# Domino_Dual_Ethernet.net
KiCad netlist of a schematic drawn in EAGLE
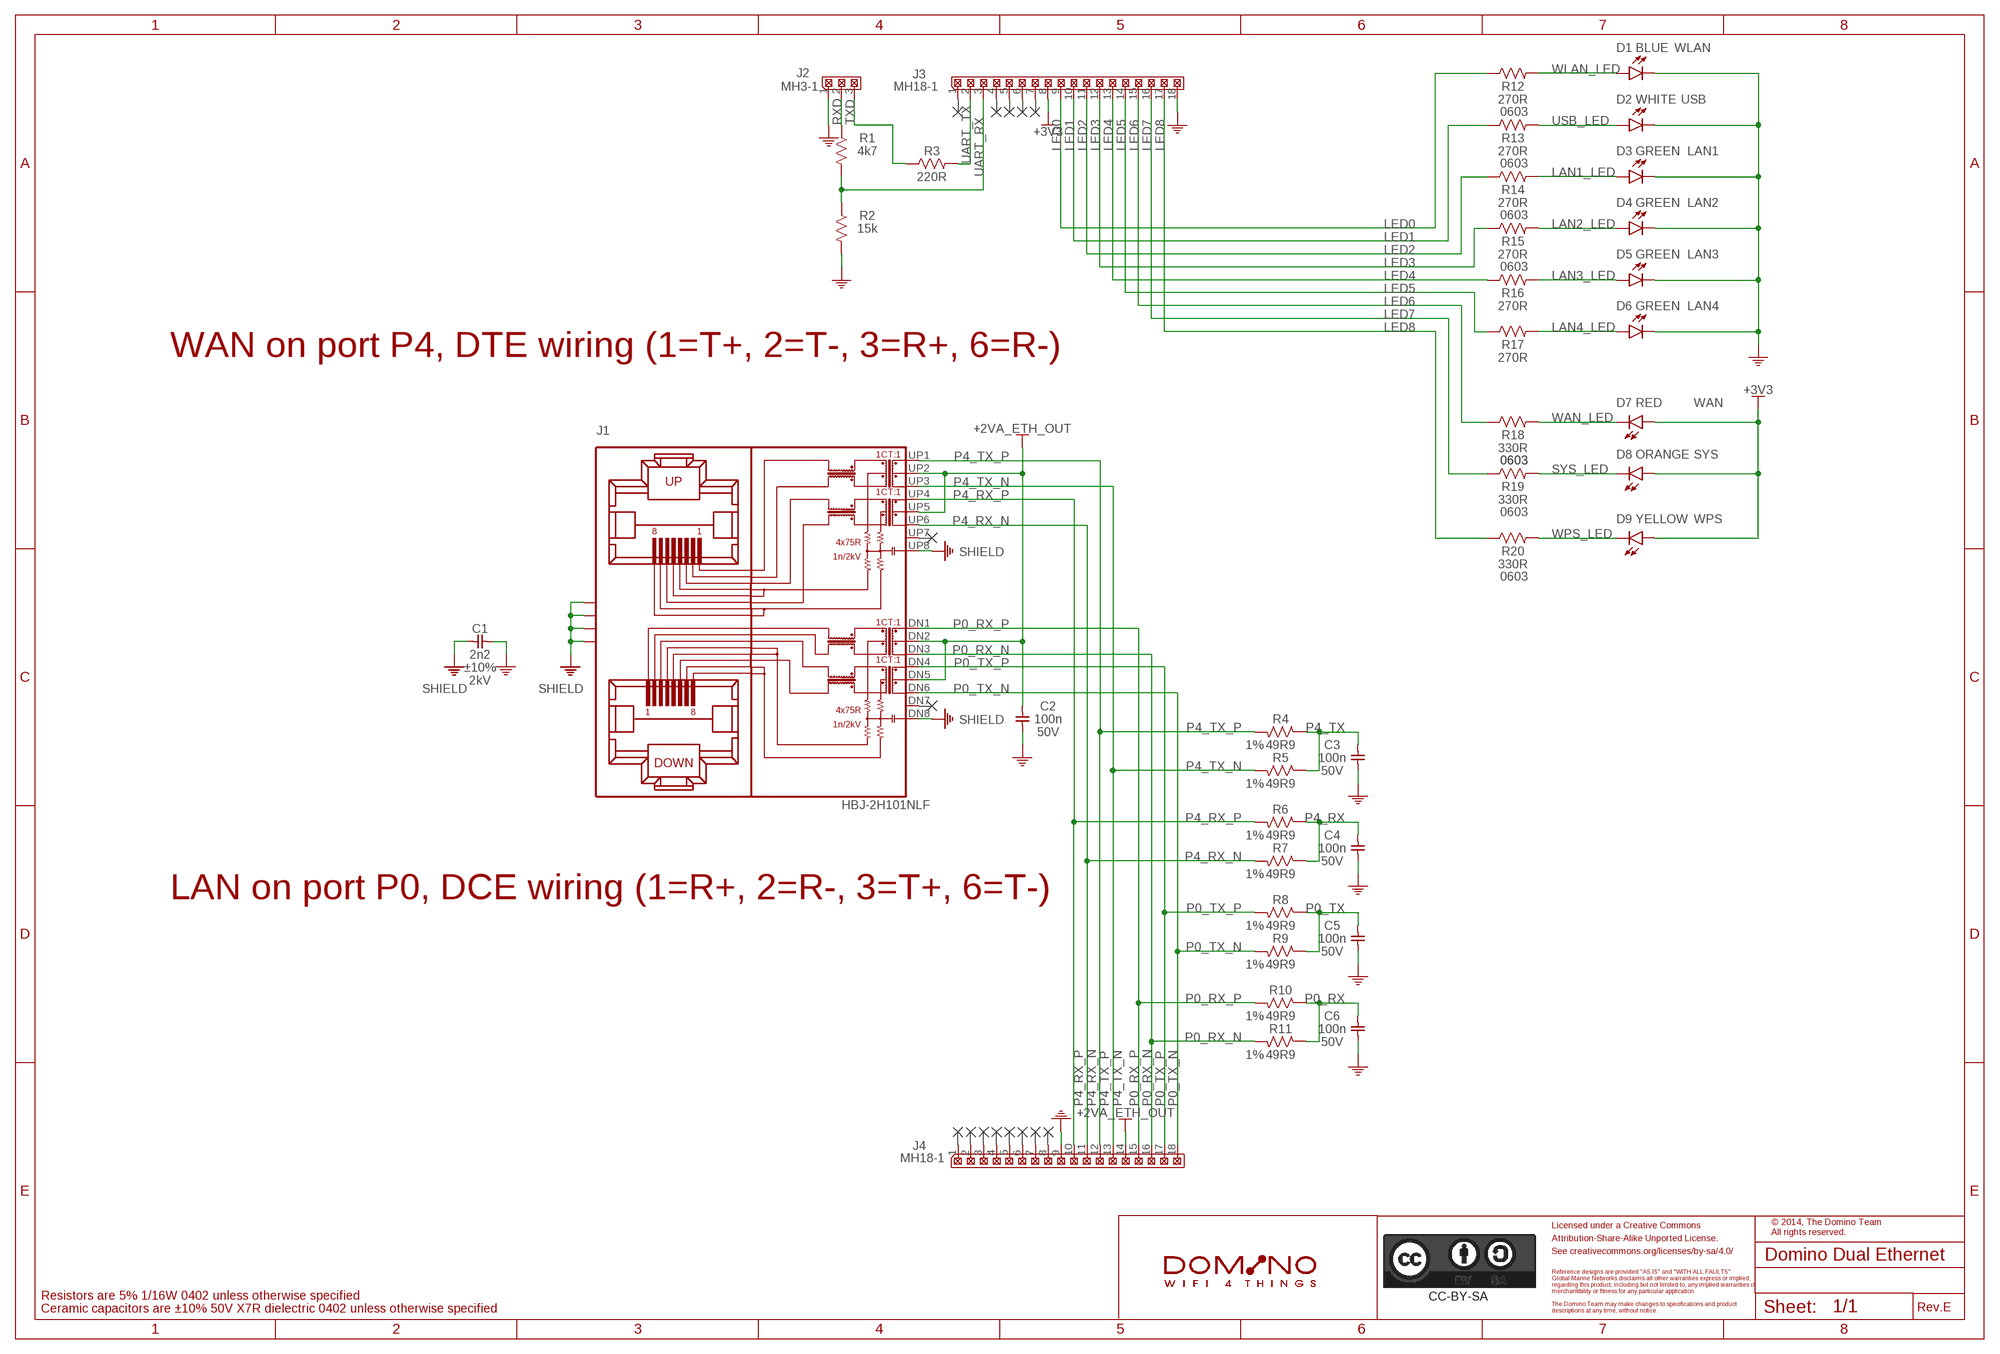
[diagram p0: schematic, sheet 1]

(export (version "E")
  (design (tool "Eeschema 10.0.6"))
  (components
    (comp (ref "C1")
      (value "2n2")
      (footprint "eagle-import:C1206")
      (fields
        (field (name "PARTNO") "C1210_2n2_X7R_10%_CER_2kV")
        (field (name "TOL") "±10%")
        (field (name "VOLT") "2kV")
      )
      (libsource (lib "eagle-import") (part "CAP_1206"))
    )
    (comp (ref "C2")
      (value "100n")
      (footprint "eagle-import:C0402")
      (fields (field (name "PARTNO") "C0402_100n_X7R_10%_CER_50V") (field (name "VOLT") "50V"))
      (libsource (lib "eagle-import") (part "CAP_0402"))
    )
    (comp (ref "C3")
      (value "100n")
      (footprint "eagle-import:C0402")
      (fields (field (name "PARTNO") "C0402_100n_X7R_10%_CER_50V") (field (name "VOLT") "50V"))
      (libsource (lib "eagle-import") (part "CAP_0402"))
    )
    (comp (ref "C4")
      (value "100n")
      (footprint "eagle-import:C0402")
      (fields (field (name "PARTNO") "C0402_100n_X7R_10%_CER_50V") (field (name "VOLT") "50V"))
      (libsource (lib "eagle-import") (part "CAP_0402"))
    )
    (comp (ref "C5")
      (value "100n")
      (footprint "eagle-import:C0402")
      (fields (field (name "PARTNO") "C0402_100n_X7R_10%_CER_50V") (field (name "VOLT") "50V"))
      (libsource (lib "eagle-import") (part "CAP_0402"))
    )
    (comp (ref "C6")
      (value "100n")
      (footprint "eagle-import:C0402")
      (fields (field (name "PARTNO") "C0402_100n_X7R_10%_CER_50V") (field (name "VOLT") "50V"))
      (libsource (lib "eagle-import") (part "CAP_0402"))
    )
    (comp (ref "CC-BY-SA1")
      (value "CC-BY-SA_LOGO")
      (footprint "eagle-import:CC-BY-SA_LOGO")
      (libsource (lib "eagle-import") (part "CC-BY-SA_LOGO"))
    )
    (comp (ref "D1")
      (value "BLUE")
      (footprint "eagle-import:LED0603")
      (fields (field (name "PARTNO") "LED0603-BLUE"))
      (libsource (lib "eagle-import") (part "LED_0603"))
    )
    (comp (ref "D2")
      (value "WHITE")
      (footprint "eagle-import:LED0603")
      (fields (field (name "PARTNO") "LED0603-WHITE"))
      (libsource (lib "eagle-import") (part "LED_0603"))
    )
    (comp (ref "D3")
      (value "GREEN")
      (footprint "eagle-import:LED0603")
      (fields (field (name "PARTNO") "LED0603-GREEN"))
      (libsource (lib "eagle-import") (part "LED_0603"))
    )
    (comp (ref "D4")
      (value "GREEN")
      (footprint "eagle-import:LED0603")
      (fields (field (name "PARTNO") "LED0603-GREEN"))
      (libsource (lib "eagle-import") (part "LED_0603"))
    )
    (comp (ref "D5")
      (value "GREEN")
      (footprint "eagle-import:LED0603")
      (fields (field (name "PARTNO") "LED0603-GREEN"))
      (libsource (lib "eagle-import") (part "LED_0603"))
    )
    (comp (ref "D6")
      (value "GREEN")
      (footprint "eagle-import:LED0603")
      (fields (field (name "PARTNO") "LED0603-GREEN"))
      (libsource (lib "eagle-import") (part "LED_0603"))
    )
    (comp (ref "D7")
      (value "RED")
      (footprint "eagle-import:LED0603")
      (fields (field (name "PARTNO") "LED0603-ORANGE"))
      (libsource (lib "eagle-import") (part "LED_0603"))
    )
    (comp (ref "D8")
      (value "ORANGE")
      (footprint "eagle-import:LED0603")
      (fields (field (name "PARTNO") "LED0603-ORANGE"))
      (libsource (lib "eagle-import") (part "LED_0603"))
    )
    (comp (ref "D9")
      (value "YELLOW")
      (footprint "eagle-import:LED0603")
      (fields (field (name "PARTNO") "LED0603-YELLOW"))
      (libsource (lib "eagle-import") (part "LED_0603"))
    )
    (comp (ref "J1")
      (value "HBJ-2H101NLF")
      (footprint "eagle-import:HBJ-2H101NLF")
      (libsource (lib "eagle-import") (part "HBJ-2H101NLF"))
    )
    (comp (ref "J2")
      (value "MH3-1")
      (footprint "eagle-import:MH3-1-0.1")
      (fields (field (name "PARTNO") "MH3-1-0.1"))
      (libsource (lib "eagle-import") (part "MH3-1"))
    )
    (comp (ref "J3")
      (value "MH18-1")
      (footprint "eagle-import:MH18-1-0.1")
      (fields (field (name "PARTNO") "MH18-1-0.1"))
      (libsource (lib "eagle-import") (part "MH18-1"))
    )
    (comp (ref "J4")
      (value "MH18-1")
      (footprint "eagle-import:MH18-1-0.1")
      (fields (field (name "PARTNO") "MH18-1-0.1"))
      (libsource (lib "eagle-import") (part "MH18-1"))
    )
    (comp (ref "L1")
      (value "DOMINO_LOGO")
      (footprint "eagle-import:DOMINO_LOGO")
      (libsource (lib "eagle-import") (part "DOMINO_LOGO"))
    )
    (comp (ref "R1")
      (value "4k7")
      (footprint "eagle-import:R0402")
      (fields (field (name "PARTNO") "R0402_4k7_5%_62.5mW"))
      (libsource (lib "eagle-import") (part "RES_0402"))
    )
    (comp (ref "R2")
      (value "15k")
      (footprint "eagle-import:R0402")
      (fields (field (name "PARTNO") "R0402_15k_5%_62.5mW"))
      (libsource (lib "eagle-import") (part "RES_0402"))
    )
    (comp (ref "R3")
      (value "220R")
      (footprint "eagle-import:R0402")
      (fields (field (name "PARTNO") "R0402_220R_5%_62.5mW"))
      (libsource (lib "eagle-import") (part "RES_0402"))
    )
    (comp (ref "R4")
      (value "49R9")
      (footprint "eagle-import:R0402")
      (fields (field (name "PARTNO") "R0402_49R9_1%_62.5mW") (field (name "TOL") "1%"))
      (libsource (lib "eagle-import") (part "RES_0402"))
    )
    (comp (ref "R5")
      (value "49R9")
      (footprint "eagle-import:R0402")
      (fields (field (name "PARTNO") "R0402_49R9_1%_62.5mW") (field (name "TOL") "1%"))
      (libsource (lib "eagle-import") (part "RES_0402"))
    )
    (comp (ref "R6")
      (value "49R9")
      (footprint "eagle-import:R0402")
      (fields (field (name "PARTNO") "R0402_49R9_1%_62.5mW") (field (name "TOL") "1%"))
      (libsource (lib "eagle-import") (part "RES_0402"))
    )
    (comp (ref "R7")
      (value "49R9")
      (footprint "eagle-import:R0402")
      (fields (field (name "PARTNO") "R0402_49R9_1%_62.5mW") (field (name "TOL") "1%"))
      (libsource (lib "eagle-import") (part "RES_0402"))
    )
    (comp (ref "R8")
      (value "49R9")
      (footprint "eagle-import:R0402")
      (fields (field (name "PARTNO") "R0402_49R9_1%_62.5mW") (field (name "TOL") "1%"))
      (libsource (lib "eagle-import") (part "RES_0402"))
    )
    (comp (ref "R9")
      (value "49R9")
      (footprint "eagle-import:R0402")
      (fields (field (name "PARTNO") "R0402_49R9_1%_62.5mW") (field (name "TOL") "1%"))
      (libsource (lib "eagle-import") (part "RES_0402"))
    )
    (comp (ref "R10")
      (value "49R9")
      (footprint "eagle-import:R0402")
      (fields (field (name "PARTNO") "R0402_49R9_1%_62.5mW") (field (name "TOL") "1%"))
      (libsource (lib "eagle-import") (part "RES_0402"))
    )
    (comp (ref "R11")
      (value "49R9")
      (footprint "eagle-import:R0402")
      (fields (field (name "PARTNO") "R0402_49R9_1%_62.5mW") (field (name "TOL") "1%"))
      (libsource (lib "eagle-import") (part "RES_0402"))
    )
    (comp (ref "R12")
      (value "270R")
      (footprint "eagle-import:R0603")
      (fields (field (name "SIZE") "0603") (field (name "PARTNO") "R0603_270R_5%_125mW"))
      (libsource (lib "eagle-import") (part "RES_0603"))
    )
    (comp (ref "R13")
      (value "270R")
      (footprint "eagle-import:R0603")
      (fields (field (name "SIZE") "0603") (field (name "PARTNO") "R0603_270R_5%_125mW"))
      (libsource (lib "eagle-import") (part "RES_0603"))
    )
    (comp (ref "R14")
      (value "270R")
      (footprint "eagle-import:R0603")
      (fields (field (name "SIZE") "0603") (field (name "PARTNO") "R0603_270R_5%_125mW"))
      (libsource (lib "eagle-import") (part "RES_0603"))
    )
    (comp (ref "R15")
      (value "270R")
      (footprint "eagle-import:R0603")
      (fields (field (name "SIZE") "0603") (field (name "PARTNO") "R0603_270R_5%_125mW"))
      (libsource (lib "eagle-import") (part "RES_0603"))
    )
    (comp (ref "R16")
      (value "270R")
      (footprint "eagle-import:R0603")
      (fields (field (name "PARTNO") "R0603_270R_5%_125mW"))
      (libsource (lib "eagle-import") (part "RES_0603"))
    )
    (comp (ref "R17")
      (value "270R")
      (footprint "eagle-import:R0603")
      (fields (field (name "SIZE") "0603") (field (name "PARTNO") "R0603_270R_5%_125mW"))
      (libsource (lib "eagle-import") (part "RES_0603"))
    )
    (comp (ref "R18")
      (value "330R")
      (footprint "eagle-import:R0603")
      (fields (field (name "SIZE") "0603") (field (name "PARTNO") "R0603_330R_5%_125mW"))
      (libsource (lib "eagle-import") (part "RES_0603"))
    )
    (comp (ref "R19")
      (value "330R")
      (footprint "eagle-import:R0603")
      (fields (field (name "SIZE") "0603") (field (name "PARTNO") "R0603_330R_5%_125mW"))
      (libsource (lib "eagle-import") (part "RES_0603"))
    )
    (comp (ref "R20")
      (value "330R")
      (footprint "eagle-import:R0603")
      (fields (field (name "SIZE") "0603") (field (name "PARTNO") "R0603_330R_5%_125mW"))
      (libsource (lib "eagle-import") (part "RES_0603"))
    )
  )
  (nets
    (net (code "1") (name "+2VA_ETH_OUT") (class "Default")
      (node (ref "C2") (pin "2") (pinfunction "2_2") (pintype "passive"))
      (node (ref "J1") (pin "DN2") (pinfunction "DR2_DN2") (pintype "passive"))
      (node (ref "J1") (pin "DN5") (pinfunction "DR5_DN5") (pintype "passive"))
      (node (ref "J1") (pin "UP2") (pinfunction "UR2_UP2") (pintype "passive"))
      (node (ref "J1") (pin "UP5") (pinfunction "UR5_UP5") (pintype "passive"))
      (node (ref "J4") (pin "14") (pinfunction "14_14") (pintype "passive"))
    )
    (net (code "2") (name "+3V3") (class "Default")
      (node (ref "D7") (pin "2") (pinfunction "A_2") (pintype "passive"))
      (node (ref "D8") (pin "2") (pinfunction "A_2") (pintype "passive"))
      (node (ref "D9") (pin "2") (pinfunction "A_2") (pintype "passive"))
      (node (ref "J3") (pin "8") (pinfunction "8_8") (pintype "passive"))
    )
    (net (code "3") (name "/LAN1_LED") (class "Default")
      (node (ref "D3") (pin "2") (pinfunction "A_2") (pintype "passive"))
      (node (ref "R14") (pin "2") (pinfunction "2_2") (pintype "passive"))
    )
    (net (code "4") (name "/LAN2_LED") (class "Default")
      (node (ref "D4") (pin "2") (pinfunction "A_2") (pintype "passive"))
      (node (ref "R15") (pin "2") (pinfunction "2_2") (pintype "passive"))
    )
    (net (code "5") (name "/LAN3_LED") (class "Default")
      (node (ref "D5") (pin "2") (pinfunction "A_2") (pintype "passive"))
      (node (ref "R16") (pin "2") (pinfunction "2_2") (pintype "passive"))
    )
    (net (code "6") (name "/LAN4_LED") (class "Default")
      (node (ref "D6") (pin "2") (pinfunction "A_2") (pintype "passive"))
      (node (ref "R17") (pin "2") (pinfunction "2_2") (pintype "passive"))
    )
    (net (code "7") (name "/LED0") (class "Default")
      (node (ref "J3") (pin "9") (pinfunction "9_9") (pintype "passive"))
      (node (ref "R12") (pin "1") (pinfunction "1_1") (pintype "passive"))
    )
    (net (code "8") (name "/LED1") (class "Default")
      (node (ref "J3") (pin "10") (pinfunction "10_10") (pintype "passive"))
      (node (ref "R13") (pin "1") (pinfunction "1_1") (pintype "passive"))
    )
    (net (code "9") (name "/LED2") (class "Default")
      (node (ref "J3") (pin "11") (pinfunction "11_11") (pintype "passive"))
      (node (ref "R14") (pin "1") (pinfunction "1_1") (pintype "passive"))
    )
    (net (code "10") (name "/LED3") (class "Default")
      (node (ref "J3") (pin "12") (pinfunction "12_12") (pintype "passive"))
      (node (ref "R15") (pin "1") (pinfunction "1_1") (pintype "passive"))
    )
    (net (code "11") (name "/LED4") (class "Default")
      (node (ref "J3") (pin "13") (pinfunction "13_13") (pintype "passive"))
      (node (ref "R16") (pin "1") (pinfunction "1_1") (pintype "passive"))
    )
    (net (code "12") (name "/LED5") (class "Default")
      (node (ref "J3") (pin "14") (pinfunction "14_14") (pintype "passive"))
      (node (ref "R17") (pin "1") (pinfunction "1_1") (pintype "passive"))
    )
    (net (code "13") (name "/LED6") (class "Default")
      (node (ref "J3") (pin "15") (pinfunction "15_15") (pintype "passive"))
      (node (ref "R18") (pin "1") (pinfunction "1_1") (pintype "passive"))
    )
    (net (code "14") (name "/LED7") (class "Default")
      (node (ref "J3") (pin "16") (pinfunction "16_16") (pintype "passive"))
      (node (ref "R19") (pin "1") (pinfunction "1_1") (pintype "passive"))
    )
    (net (code "15") (name "/LED8") (class "Default")
      (node (ref "J3") (pin "17") (pinfunction "17_17") (pintype "passive"))
      (node (ref "R20") (pin "1") (pinfunction "1_1") (pintype "passive"))
    )
    (net (code "16") (name "/P0_RX") (class "Default")
      (node (ref "C6") (pin "2") (pinfunction "2_2") (pintype "passive"))
      (node (ref "R10") (pin "1") (pinfunction "1_1") (pintype "passive"))
      (node (ref "R11") (pin "1") (pinfunction "1_1") (pintype "passive"))
    )
    (net (code "17") (name "/P0_RX_N") (class "Default")
      (node (ref "J1") (pin "DN3") (pinfunction "DR3_DN3") (pintype "passive"))
      (node (ref "J4") (pin "16") (pinfunction "16_16") (pintype "passive"))
      (node (ref "R11") (pin "2") (pinfunction "2_2") (pintype "passive"))
    )
    (net (code "18") (name "/P0_RX_P") (class "Default")
      (node (ref "J1") (pin "DN1") (pinfunction "DR1_DN1") (pintype "passive"))
      (node (ref "J4") (pin "15") (pinfunction "15_15") (pintype "passive"))
      (node (ref "R10") (pin "2") (pinfunction "2_2") (pintype "passive"))
    )
    (net (code "19") (name "/P0_TX") (class "Default")
      (node (ref "C5") (pin "2") (pinfunction "2_2") (pintype "passive"))
      (node (ref "R8") (pin "1") (pinfunction "1_1") (pintype "passive"))
      (node (ref "R9") (pin "1") (pinfunction "1_1") (pintype "passive"))
    )
    (net (code "20") (name "/P0_TX_N") (class "Default")
      (node (ref "J1") (pin "DN6") (pinfunction "DR6_DN6") (pintype "passive"))
      (node (ref "J4") (pin "18") (pinfunction "18_18") (pintype "passive"))
      (node (ref "R9") (pin "2") (pinfunction "2_2") (pintype "passive"))
    )
    (net (code "21") (name "/P0_TX_P") (class "Default")
      (node (ref "J1") (pin "DN4") (pinfunction "DR4_DN4") (pintype "passive"))
      (node (ref "J4") (pin "17") (pinfunction "17_17") (pintype "passive"))
      (node (ref "R8") (pin "2") (pinfunction "2_2") (pintype "passive"))
    )
    (net (code "22") (name "/P4_RX") (class "Default")
      (node (ref "C4") (pin "2") (pinfunction "2_2") (pintype "passive"))
      (node (ref "R6") (pin "1") (pinfunction "1_1") (pintype "passive"))
      (node (ref "R7") (pin "1") (pinfunction "1_1") (pintype "passive"))
    )
    (net (code "23") (name "/P4_RX_N") (class "Default")
      (node (ref "J1") (pin "UP6") (pinfunction "UR6_UP6") (pintype "passive"))
      (node (ref "J4") (pin "11") (pinfunction "11_11") (pintype "passive"))
      (node (ref "R7") (pin "2") (pinfunction "2_2") (pintype "passive"))
    )
    (net (code "24") (name "/P4_RX_P") (class "Default")
      (node (ref "J1") (pin "UP4") (pinfunction "UR4_UP4") (pintype "passive"))
      (node (ref "J4") (pin "10") (pinfunction "10_10") (pintype "passive"))
      (node (ref "R6") (pin "2") (pinfunction "2_2") (pintype "passive"))
    )
    (net (code "25") (name "/P4_TX") (class "Default")
      (node (ref "C3") (pin "2") (pinfunction "2_2") (pintype "passive"))
      (node (ref "R4") (pin "1") (pinfunction "1_1") (pintype "passive"))
      (node (ref "R5") (pin "1") (pinfunction "1_1") (pintype "passive"))
    )
    (net (code "26") (name "/P4_TX_N") (class "Default")
      (node (ref "J1") (pin "UP3") (pinfunction "UR3_UP3") (pintype "passive"))
      (node (ref "J4") (pin "13") (pinfunction "13_13") (pintype "passive"))
      (node (ref "R5") (pin "2") (pinfunction "2_2") (pintype "passive"))
    )
    (net (code "27") (name "/P4_TX_P") (class "Default")
      (node (ref "J1") (pin "UP1") (pinfunction "UR1_UP1") (pintype "passive"))
      (node (ref "J4") (pin "12") (pinfunction "12_12") (pintype "passive"))
      (node (ref "R4") (pin "2") (pinfunction "2_2") (pintype "passive"))
    )
    (net (code "28") (name "/RXD") (class "Default")
      (node (ref "J2") (pin "2") (pinfunction "2_2") (pintype "passive"))
      (node (ref "R1") (pin "1") (pinfunction "1_1") (pintype "passive"))
    )
    (net (code "29") (name "/SYS_LED") (class "Default")
      (node (ref "D8") (pin "1") (pinfunction "C_1") (pintype "passive"))
      (node (ref "R19") (pin "2") (pinfunction "2_2") (pintype "passive"))
    )
    (net (code "30") (name "/TXD") (class "Default")
      (node (ref "J2") (pin "3") (pinfunction "3_3") (pintype "passive"))
      (node (ref "R3") (pin "1") (pinfunction "1_1") (pintype "passive"))
    )
    (net (code "31") (name "/UART_RX") (class "Default")
      (node (ref "J3") (pin "3") (pinfunction "3_3") (pintype "passive"))
      (node (ref "R1") (pin "2") (pinfunction "2_2") (pintype "passive"))
      (node (ref "R2") (pin "1") (pinfunction "1_1") (pintype "passive"))
    )
    (net (code "32") (name "/UART_TX") (class "Default")
      (node (ref "J3") (pin "2") (pinfunction "2_2") (pintype "passive"))
      (node (ref "R3") (pin "2") (pinfunction "2_2") (pintype "passive"))
    )
    (net (code "33") (name "/USB_LED") (class "Default")
      (node (ref "D2") (pin "2") (pinfunction "A_2") (pintype "passive"))
      (node (ref "R13") (pin "2") (pinfunction "2_2") (pintype "passive"))
    )
    (net (code "34") (name "/WAN_LED") (class "Default")
      (node (ref "D7") (pin "1") (pinfunction "C_1") (pintype "passive"))
      (node (ref "R18") (pin "2") (pinfunction "2_2") (pintype "passive"))
    )
    (net (code "35") (name "/WLAN_LED") (class "Default")
      (node (ref "D1") (pin "2") (pinfunction "A_2") (pintype "passive"))
      (node (ref "R12") (pin "2") (pinfunction "2_2") (pintype "passive"))
    )
    (net (code "36") (name "/WPS_LED") (class "Default")
      (node (ref "D9") (pin "1") (pinfunction "C_1") (pintype "passive"))
      (node (ref "R20") (pin "2") (pinfunction "2_2") (pintype "passive"))
    )
    (net (code "37") (name "GND") (class "Default")
      (node (ref "C1") (pin "1") (pinfunction "1_1") (pintype "passive"))
      (node (ref "C2") (pin "1") (pinfunction "1_1") (pintype "passive"))
      (node (ref "C3") (pin "1") (pinfunction "1_1") (pintype "passive"))
      (node (ref "C4") (pin "1") (pinfunction "1_1") (pintype "passive"))
      (node (ref "C5") (pin "1") (pinfunction "1_1") (pintype "passive"))
      (node (ref "C6") (pin "1") (pinfunction "1_1") (pintype "passive"))
      (node (ref "D1") (pin "1") (pinfunction "C_1") (pintype "passive"))
      (node (ref "D2") (pin "1") (pinfunction "C_1") (pintype "passive"))
      (node (ref "D3") (pin "1") (pinfunction "C_1") (pintype "passive"))
      (node (ref "D4") (pin "1") (pinfunction "C_1") (pintype "passive"))
      (node (ref "D5") (pin "1") (pinfunction "C_1") (pintype "passive"))
      (node (ref "D6") (pin "1") (pinfunction "C_1") (pintype "passive"))
      (node (ref "J2") (pin "1") (pinfunction "1_1") (pintype "passive"))
      (node (ref "J3") (pin "18") (pinfunction "18_18") (pintype "passive"))
      (node (ref "J4") (pin "9") (pinfunction "9_9") (pintype "passive"))
      (node (ref "R2") (pin "2") (pinfunction "2_2") (pintype "passive"))
    )
    (net (code "38") (name "SHIELD") (class "Default")
      (node (ref "C1") (pin "2") (pinfunction "2_2") (pintype "passive"))
      (node (ref "J1") (pin "DN8") (pinfunction "DR8_DN8") (pintype "power_in"))
      (node (ref "J1") (pin "P$1") (pinfunction "SHIELD_P$1") (pintype "power_in"))
      (node (ref "J1") (pin "P$2") (pinfunction "SHIELD_P$2") (pintype "power_in"))
      (node (ref "J1") (pin "P$3") (pinfunction "SHIELD_P$3") (pintype "power_in"))
      (node (ref "J1") (pin "P$4") (pinfunction "SHIELD_P$4") (pintype "power_in"))
      (node (ref "J1") (pin "UP8") (pinfunction "UR8_UP8") (pintype "power_in"))
    )
    (net (code "39") (name "unconnected-(J1-DR7-PadDN7)") (class "Default")
      (node (ref "J1") (pin "DN7") (pinfunction "DR7_DN7") (pintype "no_connect"))
    )
    (net (code "40") (name "unconnected-(J1-UR7-PadUP7)") (class "Default")
      (node (ref "J1") (pin "UP7") (pinfunction "UR7_UP7") (pintype "no_connect"))
    )
    (net (code "41") (name "unconnected-(J3-Pad1)") (class "Default")
      (node (ref "J3") (pin "1") (pinfunction "1_1") (pintype "passive"))
    )
    (net (code "42") (name "unconnected-(J3-Pad4)") (class "Default")
      (node (ref "J3") (pin "4") (pinfunction "4_4") (pintype "passive"))
    )
    (net (code "43") (name "unconnected-(J3-Pad5)") (class "Default")
      (node (ref "J3") (pin "5") (pinfunction "5_5") (pintype "passive"))
    )
    (net (code "44") (name "unconnected-(J3-Pad6)") (class "Default")
      (node (ref "J3") (pin "6") (pinfunction "6_6") (pintype "passive"))
    )
    (net (code "45") (name "unconnected-(J3-Pad7)") (class "Default")
      (node (ref "J3") (pin "7") (pinfunction "7_7") (pintype "passive"))
    )
    (net (code "46") (name "unconnected-(J4-Pad1)") (class "Default")
      (node (ref "J4") (pin "1") (pinfunction "1_1") (pintype "passive"))
    )
    (net (code "47") (name "unconnected-(J4-Pad2)") (class "Default")
      (node (ref "J4") (pin "2") (pinfunction "2_2") (pintype "passive"))
    )
    (net (code "48") (name "unconnected-(J4-Pad3)") (class "Default")
      (node (ref "J4") (pin "3") (pinfunction "3_3") (pintype "passive"))
    )
    (net (code "49") (name "unconnected-(J4-Pad4)") (class "Default")
      (node (ref "J4") (pin "4") (pinfunction "4_4") (pintype "passive"))
    )
    (net (code "50") (name "unconnected-(J4-Pad5)") (class "Default")
      (node (ref "J4") (pin "5") (pinfunction "5_5") (pintype "passive"))
    )
    (net (code "51") (name "unconnected-(J4-Pad6)") (class "Default")
      (node (ref "J4") (pin "6") (pinfunction "6_6") (pintype "passive"))
    )
    (net (code "52") (name "unconnected-(J4-Pad7)") (class "Default")
      (node (ref "J4") (pin "7") (pinfunction "7_7") (pintype "passive"))
    )
    (net (code "53") (name "unconnected-(J4-Pad8)") (class "Default")
      (node (ref "J4") (pin "8") (pinfunction "8_8") (pintype "passive"))
    )
  )
)
